# STeaMi-FP3-Jauge_Batterie.net
KiCad netlist of a schematic drawn in Altium Designer
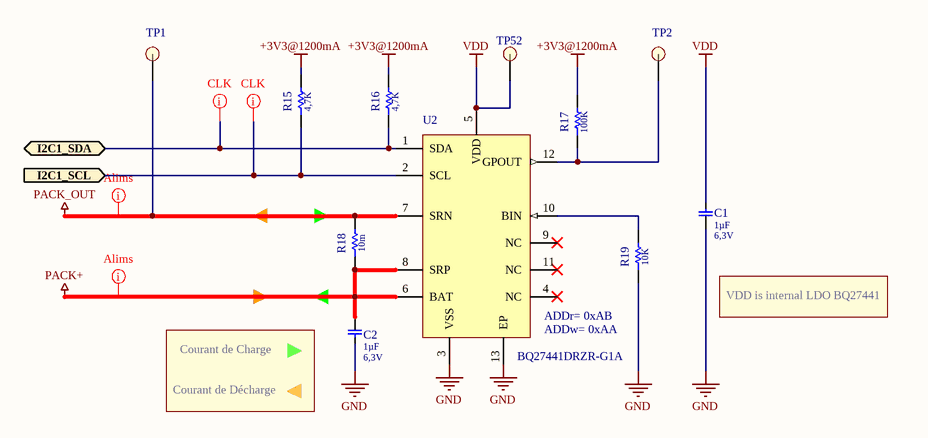
[diagram p0: STeaMi-FP3-Jauge_Batterie.SchDoc]

(export (version "E")
  (design (tool "Eeschema 10.0.6"))
  (components
    (comp (ref "C1")
      (value "~")
      (footprint "0402-CAP")
      (description "CAP CER 1µF 6,3V X5R 0402")
      (fields
        (field (name "MANUFACTURER") "Taiyo Yuden")
        (field (name "MANUFACTURER PART NUMBER") "JMK105BJ105KV-F")
        (field (name "CAPACITANCE") "1µF")
        (field (name "VOLTAGE") "6,3V")
        (field (name "CREATED BY") "EAG")
        (field (name "CHECKED BY") "*")
      )
      (libsource (lib "ComponentDB") (part "CAP_SYMBOL"))
    )
    (comp (ref "C2")
      (value "~")
      (footprint "0402-CAP")
      (description "CAP CER 1µF 6,3V X5R 0402")
      (fields
        (field (name "MANUFACTURER") "Taiyo Yuden")
        (field (name "MANUFACTURER PART NUMBER") "JMK105BJ105KV-F")
        (field (name "CAPACITANCE") "1µF")
        (field (name "VOLTAGE") "6,3V")
        (field (name "CREATED BY") "EAG")
        (field (name "CHECKED BY") "*")
      )
      (libsource (lib "ComponentDB") (part "CAP_SYMBOL"))
    )
    (comp (ref "R15")
      (value "~")
      (footprint "RESC1005X40N_0402")
      (description "RES CMS 4,7K5%-0,0625W-0402 ±100ppm/°C")
      (fields
        (field (name "MANUFACTURER") "Yageo")
        (field (name "MANUFACTURER PART NUMBER") "AC0402JR-074K7L")
        (field (name "RESISTANCE") "4,7K")
        (field (name "CREATED BY") "EAG")
      )
      (libsource (lib "ComponentDB") (part "RES_SYMBOL"))
    )
    (comp (ref "R16")
      (value "~")
      (footprint "RESC1005X40N_0402")
      (description "RES CMS 4,7K5%-0,0625W-0402 ±100ppm/°C")
      (fields
        (field (name "MANUFACTURER") "Yageo")
        (field (name "MANUFACTURER PART NUMBER") "AC0402JR-074K7L")
        (field (name "RESISTANCE") "4,7K")
        (field (name "CREATED BY") "EAG")
      )
      (libsource (lib "ComponentDB") (part "RES_SYMBOL"))
    )
    (comp (ref "R17")
      (value "~")
      (footprint "RESC1005X40N_0402")
      (description "RES CMS 100K5%-0,0625W-0402 ±100ppm/°C")
      (fields
        (field (name "MANUFACTURER") "Yageo")
        (field (name "MANUFACTURER PART NUMBER") "RC0402JR-07100KL")
        (field (name "RESISTANCE") "100K")
        (field (name "CREATED BY") "EAG")
      )
      (libsource (lib "ComponentDB") (part "RES_SYMBOL"))
    )
    (comp (ref "R18")
      (value "~")
      (footprint "RESC1005X40N_0402")
      (description "RES CMS 10m1%-0,2W-0402 ±0ppm/°C")
      (fields
        (field (name "MANUFACTURER") "Panasonic")
        (field (name "MANUFACTURER PART NUMBER") "ERJ-2LWFR010X")
        (field (name "RESISTANCE") "10m")
        (field (name "CREATED BY") "EAG")
      )
      (libsource (lib "ComponentDB") (part "RES_SYMBOL"))
    )
    (comp (ref "R19")
      (value "~")
      (footprint "RESC1005X40N_0402")
      (description "RES CMS 10K1%-0,0625W-0402 ±100ppm/°C")
      (fields
        (field (name "MANUFACTURER") "Yageo")
        (field (name "MANUFACTURER PART NUMBER") "AC0402FR-1310KL")
        (field (name "RESISTANCE") "10K")
        (field (name "CREATED BY") "EAG")
      )
      (libsource (lib "ComponentDB") (part "RES_SYMBOL"))
    )
    (comp (ref "TP1")
      (value "PAD")
      (footprint "Testpoint 1mm")
      (description "TESTPOINTPAD")
      (fields
        (field (name "MANUFACTURER") "Smartembed")
        (field (name "MANUFACTURER PART NUMBER") "TESTPOINT")
        (field (name "CREATED BY") "EAG")
      )
      (libsource (lib "ComponentDB") (part "TESTPOINT"))
    )
    (comp (ref "TP2")
      (value "PAD")
      (footprint "Testpoint 1mm")
      (description "TESTPOINTPAD")
      (fields
        (field (name "MANUFACTURER") "Smartembed")
        (field (name "MANUFACTURER PART NUMBER") "TESTPOINT")
        (field (name "CREATED BY") "EAG")
      )
      (libsource (lib "ComponentDB") (part "TESTPOINT"))
    )
    (comp (ref "TP52")
      (value "PAD")
      (footprint "Testpoint 1mm")
      (description "TESTPOINTPAD")
      (fields
        (field (name "MANUFACTURER") "Smartembed")
        (field (name "MANUFACTURER PART NUMBER") "TESTPOINT")
        (field (name "CREATED BY") "EAG")
      )
      (libsource (lib "ComponentDB") (part "TESTPOINT"))
    )
    (comp (ref "U2")
      (value "~")
      (footprint "BQ27441DRZRG1A")
      (description "LiCoO2, Li-Ion, Indicateur de charge batterie, alimentation 2.45 V à 4.5 V, interface I2C, SON-12")
      (fields
        (field (name "MANUFACTURER") "Texas Instruments")
        (field (name "MANUFACTURER PART NUMBER") "BQ27441DRZR-G1A")
        (field (name "PART NUMBER") "BQ27441DRZR-G1A")
        (field (name "CREATED BY") "MSA")
        (field (name "CHECKED BY") "*")
      )
      (libsource (lib "ComponentDB") (part "BQ27441DRZR-G1A"))
    )
  )
  (nets
    (net (code "1") (name "+3V3@1200mA") (class "Default")
      (node (ref "R15") (pin "2") (pinfunction "2_2") (pintype "passive"))
      (node (ref "R16") (pin "2") (pinfunction "2_2") (pintype "passive"))
      (node (ref "R17") (pin "2") (pinfunction "2_2") (pintype "passive"))
    )
    (net (code "2") (name "/I2C1_SCL") (class "Default")
      (node (ref "R15") (pin "1") (pinfunction "1_1") (pintype "passive"))
      (node (ref "U2") (pin "2") (pinfunction "SCL_2") (pintype "passive"))
    )
    (net (code "3") (name "/I2C1_SDA") (class "Default")
      (node (ref "R16") (pin "1") (pinfunction "1_1") (pintype "passive"))
      (node (ref "U2") (pin "1") (pinfunction "SDA_1") (pintype "passive"))
    )
    (net (code "4") (name "GND") (class "Default")
      (node (ref "C1") (pin "1") (pinfunction "1_1") (pintype "passive"))
      (node (ref "C2") (pin "2") (pinfunction "2_2") (pintype "passive"))
      (node (ref "R19") (pin "1") (pinfunction "1_1") (pintype "passive"))
      (node (ref "U2") (pin "13") (pinfunction "EP_13") (pintype "passive"))
      (node (ref "U2") (pin "3") (pinfunction "VSS_3") (pintype "passive"))
    )
    (net (code "5") (name "Net-(U2-BIN)") (class "Default")
      (node (ref "R19") (pin "2") (pinfunction "2_2") (pintype "passive"))
      (node (ref "U2") (pin "10") (pinfunction "BIN_10") (pintype "input"))
    )
    (net (code "6") (name "Net-(U2-GPOUT)") (class "Default")
      (node (ref "R17") (pin "1") (pinfunction "1_1") (pintype "passive"))
      (node (ref "TP2") (pin "1") (pinfunction "1_1") (pintype "passive"))
      (node (ref "U2") (pin "12") (pinfunction "GPOUT_12") (pintype "output"))
    )
    (net (code "7") (name "PACK+") (class "Default")
      (node (ref "C2") (pin "1") (pinfunction "1_1") (pintype "passive"))
      (node (ref "R18") (pin "1") (pinfunction "1_1") (pintype "passive"))
      (node (ref "U2") (pin "6") (pinfunction "BAT_6") (pintype "passive"))
      (node (ref "U2") (pin "8") (pinfunction "SRP_8") (pintype "passive"))
    )
    (net (code "8") (name "PACK_OUT") (class "Default")
      (node (ref "R18") (pin "2") (pinfunction "2_2") (pintype "passive"))
      (node (ref "TP1") (pin "1") (pinfunction "1_1") (pintype "passive"))
      (node (ref "U2") (pin "7") (pinfunction "SRN_7") (pintype "passive"))
    )
    (net (code "9") (name "VDD") (class "Default")
      (node (ref "C1") (pin "2") (pinfunction "2_2") (pintype "passive"))
      (node (ref "TP52") (pin "1") (pinfunction "1_1") (pintype "passive"))
      (node (ref "U2") (pin "5") (pinfunction "VDD_5") (pintype "power_in"))
    )
    (net (code "10") (name "unconnected-(U2-NC-Pad4)") (class "Default")
      (node (ref "U2") (pin "4") (pinfunction "NC_4") (pintype "passive+no_connect"))
    )
    (net (code "11") (name "unconnected-(U2-NC-Pad9)") (class "Default")
      (node (ref "U2") (pin "9") (pinfunction "NC_9") (pintype "passive+no_connect"))
    )
    (net (code "12") (name "unconnected-(U2-NC-Pad11)") (class "Default")
      (node (ref "U2") (pin "11") (pinfunction "NC_11") (pintype "passive+no_connect"))
    )
  )
)
